# light_sensor_and_buzzer_board.net
KiCad netlist of a schematic drawn in EAGLE
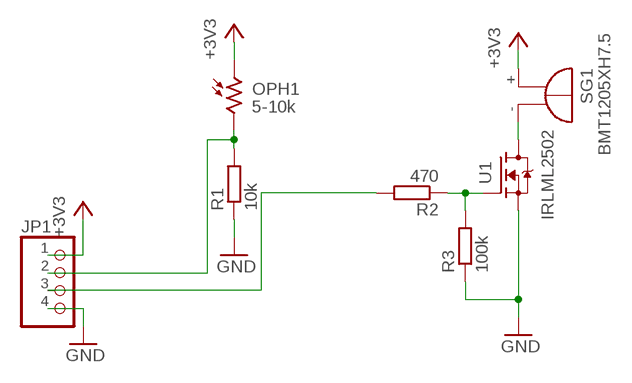
[diagram p0: schematic, sheet 1]

(export (version "E")
  (design (tool "Eeschema 10.0.6"))
  (components
    (comp (ref "JP1")
      (value "PINHD-1X4")
      (footprint "eagle-import:1X04")
      (libsource (lib "eagle-import") (part "PINHD-1X4"))
    )
    (comp (ref "OPH1")
      (value "5-10k")
      (footprint "eagle-import:VT900")
      (libsource (lib "eagle-import") (part "VT90N1"))
    )
    (comp (ref "R1")
      (value "10k")
      (footprint "eagle-import:R1206")
      (libsource (lib "eagle-import") (part "R-EU_R1206"))
    )
    (comp (ref "R2")
      (value "470")
      (footprint "eagle-import:R1206")
      (libsource (lib "eagle-import") (part "R-EU_R1206"))
    )
    (comp (ref "R3")
      (value "100k")
      (footprint "eagle-import:R1206")
      (libsource (lib "eagle-import") (part "R-EU_R1206"))
    )
    (comp (ref "SG1")
      (value "BMT1205XH7.5")
      (footprint "eagle-import:BMT1205XH7.5")
      (libsource (lib "eagle-import") (part "BMT1205XH7.5"))
    )
    (comp (ref "U1")
      (value "IRLML2502")
      (footprint "eagle-import:SOT23")
      (fields (field (name "MF") "Infineon") (field (name "MP") "IRLML2502TRPBF"))
      (libsource (lib "eagle-import") (part "IRLML2502TRPBF"))
    )
  )
  (nets
    (net (code "1") (name "+3V3") (class "Default")
      (node (ref "JP1") (pin "1") (pinfunction "1_1") (pintype "passive"))
      (node (ref "OPH1") (pin "1") (pinfunction "1_1") (pintype "passive"))
      (node (ref "SG1") (pin "+") (pinfunction "+_+") (pintype "passive"))
    )
    (net (code "2") (name "GND") (class "Default")
      (node (ref "JP1") (pin "4") (pinfunction "4_4") (pintype "passive"))
      (node (ref "R1") (pin "1") (pinfunction "1_1") (pintype "passive"))
      (node (ref "R3") (pin "1") (pinfunction "1_1") (pintype "passive"))
      (node (ref "U1") (pin "2") (pinfunction "S_2") (pintype "passive"))
    )
    (net (code "3") (name "Net-(JP1-Pad2)") (class "Default")
      (node (ref "JP1") (pin "2") (pinfunction "2_2") (pintype "passive"))
      (node (ref "OPH1") (pin "2") (pinfunction "2_2") (pintype "passive"))
      (node (ref "R1") (pin "2") (pinfunction "2_2") (pintype "passive"))
    )
    (net (code "4") (name "Net-(JP1-Pad3)") (class "Default")
      (node (ref "JP1") (pin "3") (pinfunction "3_3") (pintype "passive"))
      (node (ref "R2") (pin "2") (pinfunction "2_2") (pintype "passive"))
    )
    (net (code "5") (name "Net-(U1-D)") (class "Default")
      (node (ref "SG1") (pin "-") (pinfunction "-_-") (pintype "passive"))
      (node (ref "U1") (pin "3") (pinfunction "D_3") (pintype "passive"))
    )
    (net (code "6") (name "Net-(U1-G)") (class "Default")
      (node (ref "R2") (pin "1") (pinfunction "1_1") (pintype "passive"))
      (node (ref "R3") (pin "2") (pinfunction "2_2") (pintype "passive"))
      (node (ref "U1") (pin "1") (pinfunction "G_1") (pintype "passive"))
    )
  )
)
